# Fali_Potis.net
KiCad netlist of a schematic drawn in EAGLE
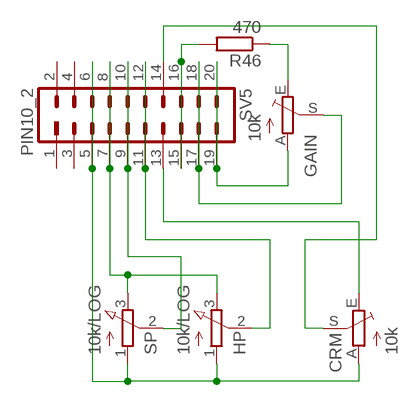
[diagram p0: schematic, sheet 1]

(export (version "E")
  (design (tool "Eeschema 10.0.6"))
  (components
    (comp (ref "CRM")
      (value "10k")
      (footprint "eagle-import:PT-10S")
      (libsource (lib "eagle-import") (part "TRIM_EU-PT10S"))
    )
    (comp (ref "GAIN")
      (value "10k")
      (footprint "eagle-import:PT-10S")
      (libsource (lib "eagle-import") (part "TRIM_EU-PT10S"))
    )
    (comp (ref "HP")
      (value "10k/LOG")
      (footprint "eagle-import:3RP_1610N")
      (libsource (lib "eagle-import") (part "3RP/1610N"))
    )
    (comp (ref "R46")
      (value "470")
      (footprint "eagle-import:R0805")
      (libsource (lib "eagle-import") (part "R-EU_R0805"))
    )
    (comp (ref "SP")
      (value "10k/LOG")
      (footprint "eagle-import:3RP_1610N")
      (libsource (lib "eagle-import") (part "3RP/1610N"))
    )
    (comp (ref "SV5")
      (value "PIN10_2")
      (footprint "eagle-import:PIN10_2")
      (libsource (lib "eagle-import") (part "PIN10_2"))
    )
  )
  (nets
    (net (code "1") (name "Net-(CRM-PadE)") (class "Default")
      (node (ref "CRM") (pin "E") (pinfunction "E_E") (pintype "passive"))
      (node (ref "SV5") (pin "13") (pinfunction "13_13") (pintype "passive"))
    )
    (net (code "2") (name "Net-(CRM-PadS)") (class "Default")
      (node (ref "CRM") (pin "S") (pinfunction "S_S") (pintype "passive"))
      (node (ref "SV5") (pin "14") (pinfunction "14_14") (pintype "passive"))
    )
    (net (code "3") (name "Net-(GAIN-PadA)") (class "Default")
      (node (ref "GAIN") (pin "A") (pinfunction "A_A") (pintype "passive"))
      (node (ref "SV5") (pin "19") (pinfunction "19_19") (pintype "passive"))
      (node (ref "SV5") (pin "20") (pinfunction "20_20") (pintype "passive"))
    )
    (net (code "4") (name "Net-(GAIN-PadE)") (class "Default")
      (node (ref "GAIN") (pin "E") (pinfunction "E_E") (pintype "passive"))
      (node (ref "R46") (pin "1") (pinfunction "1_1") (pintype "passive"))
    )
    (net (code "5") (name "Net-(GAIN-PadS)") (class "Default")
      (node (ref "GAIN") (pin "S") (pinfunction "S_S") (pintype "passive"))
      (node (ref "SV5") (pin "17") (pinfunction "17_17") (pintype "passive"))
      (node (ref "SV5") (pin "18") (pinfunction "18_18") (pintype "passive"))
    )
    (net (code "6") (name "Net-(HP-A)") (class "Default")
      (node (ref "CRM") (pin "A") (pinfunction "A_A") (pintype "passive"))
      (node (ref "HP") (pin "1") (pinfunction "A_1") (pintype "passive"))
      (node (ref "SP") (pin "1") (pinfunction "A_1") (pintype "passive"))
      (node (ref "SV5") (pin "5") (pinfunction "5_5") (pintype "passive"))
      (node (ref "SV5") (pin "6") (pinfunction "6_6") (pintype "passive"))
    )
    (net (code "7") (name "Net-(HP-E)") (class "Default")
      (node (ref "HP") (pin "3") (pinfunction "E_3") (pintype "passive"))
      (node (ref "SP") (pin "3") (pinfunction "E_3") (pintype "passive"))
      (node (ref "SV5") (pin "7") (pinfunction "7_7") (pintype "passive"))
      (node (ref "SV5") (pin "8") (pinfunction "8_8") (pintype "passive"))
    )
    (net (code "8") (name "Net-(HP-S)") (class "Default")
      (node (ref "HP") (pin "2") (pinfunction "S_2") (pintype "passive"))
      (node (ref "SV5") (pin "11") (pinfunction "11_11") (pintype "passive"))
      (node (ref "SV5") (pin "12") (pinfunction "12_12") (pintype "passive"))
    )
    (net (code "9") (name "Net-(R46-Pad2)") (class "Default")
      (node (ref "R46") (pin "2") (pinfunction "2_2") (pintype "passive"))
      (node (ref "SV5") (pin "15") (pinfunction "15_15") (pintype "passive"))
      (node (ref "SV5") (pin "16") (pinfunction "16_16") (pintype "passive"))
    )
    (net (code "10") (name "Net-(SP-S)") (class "Default")
      (node (ref "SP") (pin "2") (pinfunction "S_2") (pintype "passive"))
      (node (ref "SV5") (pin "10") (pinfunction "10_10") (pintype "passive"))
      (node (ref "SV5") (pin "9") (pinfunction "9_9") (pintype "passive"))
    )
    (net (code "11") (name "unconnected-(SV5-Pad1)") (class "Default")
      (node (ref "SV5") (pin "1") (pinfunction "1_1") (pintype "passive"))
    )
    (net (code "12") (name "unconnected-(SV5-Pad2)") (class "Default")
      (node (ref "SV5") (pin "2") (pinfunction "2_2") (pintype "passive"))
    )
    (net (code "13") (name "unconnected-(SV5-Pad3)") (class "Default")
      (node (ref "SV5") (pin "3") (pinfunction "3_3") (pintype "passive"))
    )
    (net (code "14") (name "unconnected-(SV5-Pad4)") (class "Default")
      (node (ref "SV5") (pin "4") (pinfunction "4_4") (pintype "passive"))
    )
  )
)
